# module-buttons.net
KiCad netlist of a schematic drawn in EAGLE
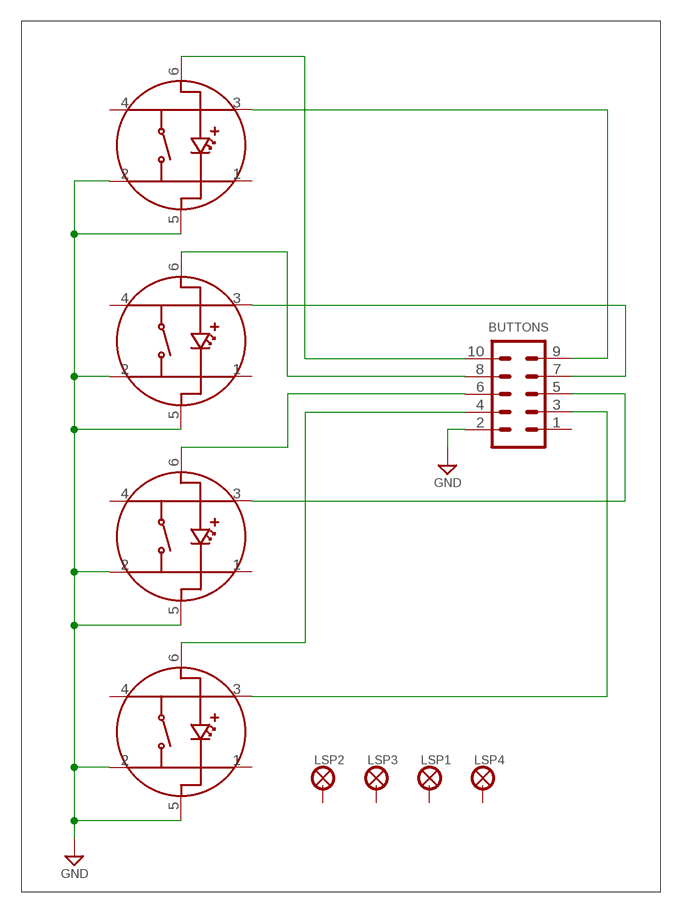
[diagram p0: schematic, sheet 1]

(export (version "E")
  (design (tool "Eeschema 10.0.6"))
  (components
    (comp (ref "BTN1")
      (value "BUTTON-TL1265")
      (footprint "eagle-import:BUTTON-TL1265")
      (libsource (lib "eagle-import") (part "BUTTON-TL1265"))
    )
    (comp (ref "BTN2")
      (value "BUTTON-TL1265")
      (footprint "eagle-import:BUTTON-TL1265")
      (libsource (lib "eagle-import") (part "BUTTON-TL1265"))
    )
    (comp (ref "BTN3")
      (value "BUTTON-TL1265")
      (footprint "eagle-import:BUTTON-TL1265")
      (libsource (lib "eagle-import") (part "BUTTON-TL1265"))
    )
    (comp (ref "BTN4")
      (value "BUTTON-TL1265")
      (footprint "eagle-import:BUTTON-TL1265")
      (libsource (lib "eagle-import") (part "BUTTON-TL1265"))
    )
    (comp (ref "BUTTONS")
      (value "MA05-2")
      (footprint "eagle-import:MA05-2")
      (libsource (lib "eagle-import") (part "MA05-2"))
    )
    (comp (ref "LSP1")
      (value "LSP27")
      (footprint "eagle-import:LSP27")
      (libsource (lib "eagle-import") (part "LSP27"))
    )
    (comp (ref "LSP2")
      (value "LSP27")
      (footprint "eagle-import:LSP27")
      (libsource (lib "eagle-import") (part "LSP27"))
    )
    (comp (ref "LSP3")
      (value "LSP27")
      (footprint "eagle-import:LSP27")
      (libsource (lib "eagle-import") (part "LSP27"))
    )
    (comp (ref "LSP4")
      (value "LSP27")
      (footprint "eagle-import:LSP27")
      (libsource (lib "eagle-import") (part "LSP27"))
    )
  )
  (nets
    (net (code "1") (name "GND") (class "Default")
      (node (ref "BTN1") (pin "2") (pinfunction "2_2") (pintype "bidirectional"))
      (node (ref "BTN1") (pin "5") (pinfunction "5_5") (pintype "bidirectional"))
      (node (ref "BTN2") (pin "2") (pinfunction "2_2") (pintype "bidirectional"))
      (node (ref "BTN2") (pin "5") (pinfunction "5_5") (pintype "bidirectional"))
      (node (ref "BTN3") (pin "2") (pinfunction "2_2") (pintype "bidirectional"))
      (node (ref "BTN3") (pin "5") (pinfunction "5_5") (pintype "bidirectional"))
      (node (ref "BTN4") (pin "2") (pinfunction "2_2") (pintype "bidirectional"))
      (node (ref "BTN4") (pin "5") (pinfunction "5_5") (pintype "bidirectional"))
      (node (ref "BUTTONS") (pin "2") (pinfunction "2_2") (pintype "passive"))
    )
    (net (code "2") (name "Net-(BTN1-Pad3)") (class "Default")
      (node (ref "BTN1") (pin "3") (pinfunction "3_3") (pintype "bidirectional"))
      (node (ref "BUTTONS") (pin "9") (pinfunction "9_9") (pintype "passive"))
    )
    (net (code "3") (name "Net-(BTN1-Pad6)") (class "Default")
      (node (ref "BTN1") (pin "6") (pinfunction "6_6") (pintype "bidirectional"))
      (node (ref "BUTTONS") (pin "10") (pinfunction "10_10") (pintype "passive"))
    )
    (net (code "4") (name "Net-(BTN2-Pad3)") (class "Default")
      (node (ref "BTN2") (pin "3") (pinfunction "3_3") (pintype "bidirectional"))
      (node (ref "BUTTONS") (pin "7") (pinfunction "7_7") (pintype "passive"))
    )
    (net (code "5") (name "Net-(BTN2-Pad6)") (class "Default")
      (node (ref "BTN2") (pin "6") (pinfunction "6_6") (pintype "bidirectional"))
      (node (ref "BUTTONS") (pin "8") (pinfunction "8_8") (pintype "passive"))
    )
    (net (code "6") (name "Net-(BTN3-Pad3)") (class "Default")
      (node (ref "BTN3") (pin "3") (pinfunction "3_3") (pintype "bidirectional"))
      (node (ref "BUTTONS") (pin "5") (pinfunction "5_5") (pintype "passive"))
    )
    (net (code "7") (name "Net-(BTN3-Pad6)") (class "Default")
      (node (ref "BTN3") (pin "6") (pinfunction "6_6") (pintype "bidirectional"))
      (node (ref "BUTTONS") (pin "6") (pinfunction "6_6") (pintype "passive"))
    )
    (net (code "8") (name "Net-(BTN4-Pad3)") (class "Default")
      (node (ref "BTN4") (pin "3") (pinfunction "3_3") (pintype "bidirectional"))
      (node (ref "BUTTONS") (pin "3") (pinfunction "3_3") (pintype "passive"))
    )
    (net (code "9") (name "Net-(BTN4-Pad6)") (class "Default")
      (node (ref "BTN4") (pin "6") (pinfunction "6_6") (pintype "bidirectional"))
      (node (ref "BUTTONS") (pin "4") (pinfunction "4_4") (pintype "passive"))
    )
    (net (code "10") (name "unconnected-(BTN1-Pad1)") (class "Default")
      (node (ref "BTN1") (pin "1") (pinfunction "1_1") (pintype "bidirectional"))
    )
    (net (code "11") (name "unconnected-(BTN1-Pad4)") (class "Default")
      (node (ref "BTN1") (pin "4") (pinfunction "4_4") (pintype "bidirectional"))
    )
    (net (code "12") (name "unconnected-(BTN2-Pad1)") (class "Default")
      (node (ref "BTN2") (pin "1") (pinfunction "1_1") (pintype "bidirectional"))
    )
    (net (code "13") (name "unconnected-(BTN2-Pad4)") (class "Default")
      (node (ref "BTN2") (pin "4") (pinfunction "4_4") (pintype "bidirectional"))
    )
    (net (code "14") (name "unconnected-(BTN3-Pad1)") (class "Default")
      (node (ref "BTN3") (pin "1") (pinfunction "1_1") (pintype "bidirectional"))
    )
    (net (code "15") (name "unconnected-(BTN3-Pad4)") (class "Default")
      (node (ref "BTN3") (pin "4") (pinfunction "4_4") (pintype "bidirectional"))
    )
    (net (code "16") (name "unconnected-(BTN4-Pad1)") (class "Default")
      (node (ref "BTN4") (pin "1") (pinfunction "1_1") (pintype "bidirectional"))
    )
    (net (code "17") (name "unconnected-(BTN4-Pad4)") (class "Default")
      (node (ref "BTN4") (pin "4") (pinfunction "4_4") (pintype "bidirectional"))
    )
    (net (code "18") (name "unconnected-(BUTTONS-Pad1)") (class "Default")
      (node (ref "BUTTONS") (pin "1") (pinfunction "1_1") (pintype "passive"))
    )
    (net (code "19") (name "unconnected-(LSP1-PadMP)") (class "Default")
      (node (ref "LSP1") (pin "MP") (pinfunction "MP_MP") (pintype "passive"))
    )
    (net (code "20") (name "unconnected-(LSP2-PadMP)") (class "Default")
      (node (ref "LSP2") (pin "MP") (pinfunction "MP_MP") (pintype "passive"))
    )
    (net (code "21") (name "unconnected-(LSP3-PadMP)") (class "Default")
      (node (ref "LSP3") (pin "MP") (pinfunction "MP_MP") (pintype "passive"))
    )
    (net (code "22") (name "unconnected-(LSP4-PadMP)") (class "Default")
      (node (ref "LSP4") (pin "MP") (pinfunction "MP_MP") (pintype "passive"))
    )
  )
)
